# MotoLogger_Schematic.net
KiCad netlist of a schematic drawn in EasyEDA
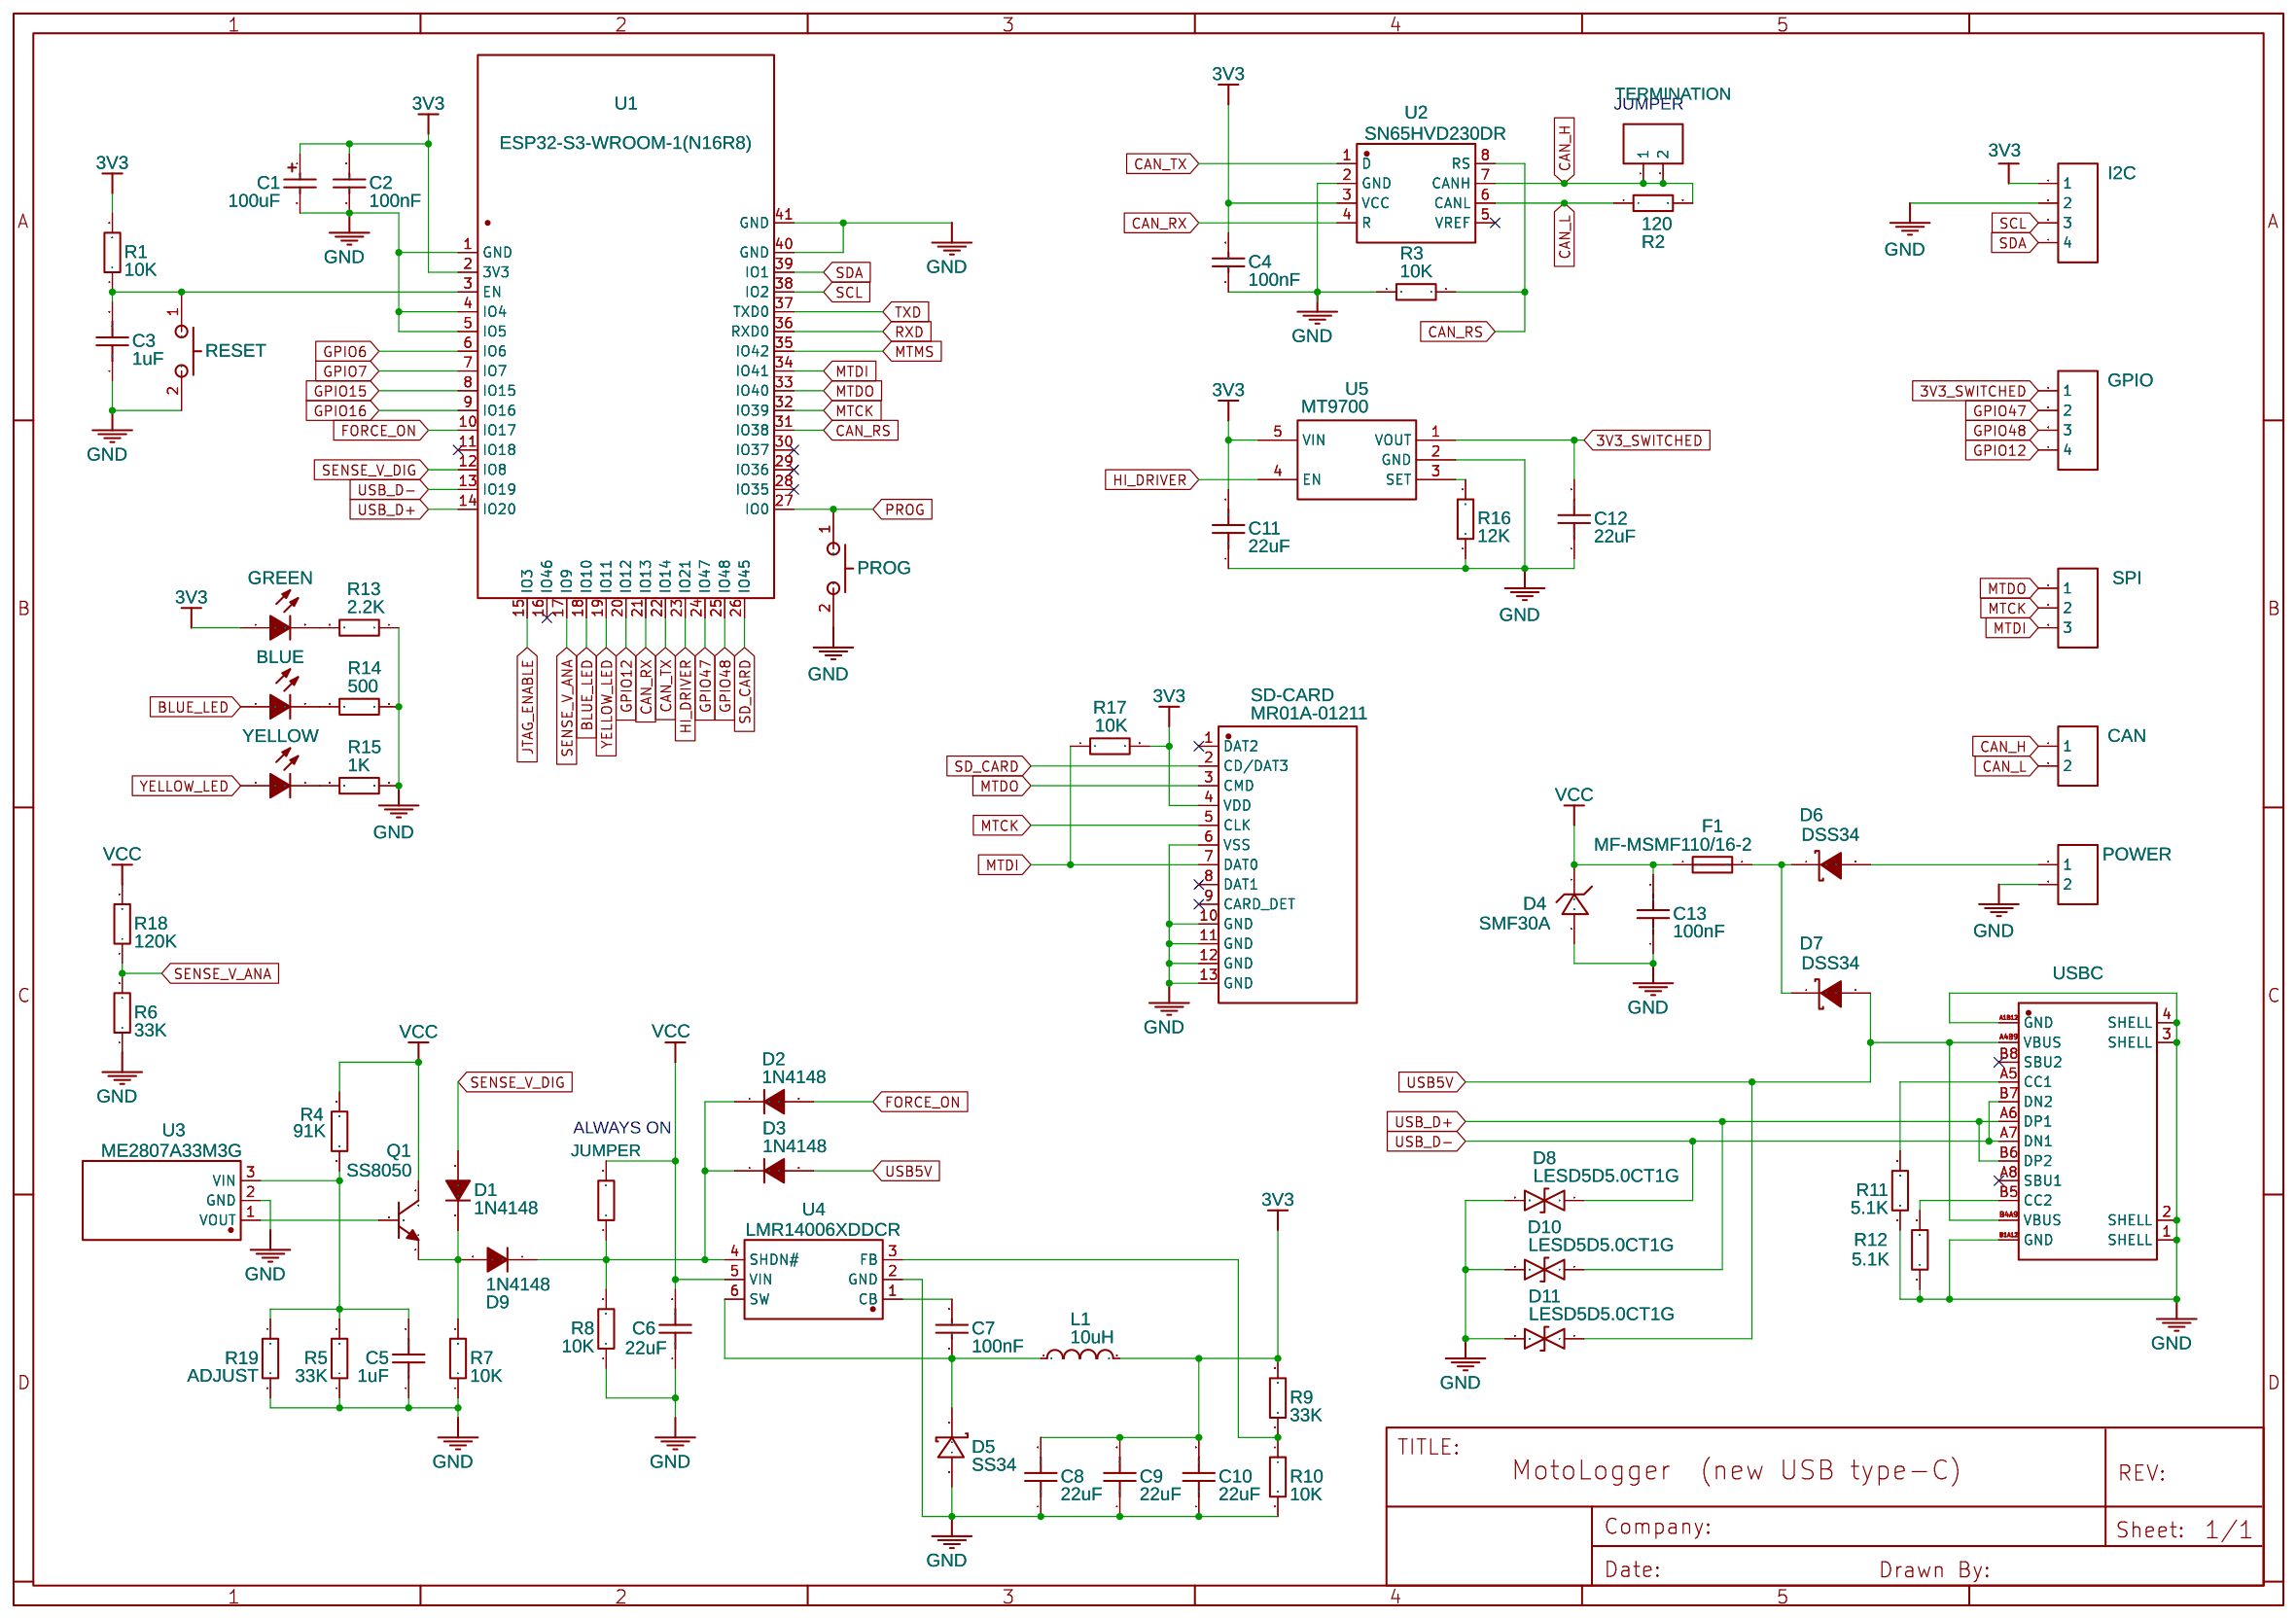
[diagram p0: schematic sheet]

(export (version "E")
  (design (tool "Eeschema 10.0.6"))
  (components
    (comp (ref "BLUE")
      (value "19-217/BHC-ZL1M2RY/3T")
      (fields (field (name "Manufacturer") "EVERLIGHT"))
      (libsource (lib "") (part "19-217/BHC-ZL1M2RY/3T"))
    )
    (comp (ref "C1")
      (value "100uF")
      (fields (field (name "Manufacturer Part") "TAJB107K006RNJ") (field (name "Manufacturer") "AVX"))
      (libsource (lib "") (part "TAJB107K006RNJ"))
    )
    (comp (ref "C2")
      (value "100nF")
      (fields (field (name "Manufacturer Part") "CL05B104KO5NNNC") (field (name "Manufacturer") "SAMSUNG"))
      (libsource (lib "") (part "CL05B104KO5NNNC"))
    )
    (comp (ref "C3")
      (value "1uF")
      (fields (field (name "Manufacturer Part") "CL05A105KA5NQNC") (field (name "Manufacturer") "SAMSUNG"))
      (libsource (lib "") (part "CL05A105KA5NQNC"))
    )
    (comp (ref "C4")
      (value "100nF")
      (fields (field (name "Manufacturer Part") "CL05B104KO5NNNC") (field (name "Manufacturer") "SAMSUNG"))
      (libsource (lib "") (part "CL05B104KO5NNNC"))
    )
    (comp (ref "C5")
      (value "1uF")
      (fields (field (name "Manufacturer Part") "CL05A105KA5NQNC") (field (name "Manufacturer") "SAMSUNG"))
      (libsource (lib "") (part "CL05A105KA5NQNC_1"))
    )
    (comp (ref "C6")
      (value "22uF")
      (fields
        (field (name "Manufacturer Part") "CL21A226MAYNNNE")
        (field (name "Manufacturer") "Samsung Electro-Mechanics")
      )
      (libsource (lib "") (part "CL21A226MAYNNNE"))
    )
    (comp (ref "C7")
      (value "100nF")
      (fields (field (name "Manufacturer Part") "CL05B104KO5NNNC") (field (name "Manufacturer") "SAMSUNG"))
      (libsource (lib "") (part "CL05B104KO5NNNC"))
    )
    (comp (ref "C8")
      (value "22uF")
      (fields (field (name "Manufacturer Part") "CL10A226MQ8NRNC") (field (name "Manufacturer") "SAMSUNG"))
      (libsource (lib "") (part "CL10A226MQ8NRNC"))
    )
    (comp (ref "C9")
      (value "22uF")
      (fields (field (name "Manufacturer Part") "CL10A226MQ8NRNC") (field (name "Manufacturer") "SAMSUNG"))
      (libsource (lib "") (part "CL10A226MQ8NRNC"))
    )
    (comp (ref "C10")
      (value "22uF")
      (fields (field (name "Manufacturer Part") "CL10A226MQ8NRNC") (field (name "Manufacturer") "SAMSUNG"))
      (libsource (lib "") (part "CL10A226MQ8NRNC"))
    )
    (comp (ref "C11")
      (value "22uF")
      (fields (field (name "Manufacturer Part") "CL10A226MQ8NRNC") (field (name "Manufacturer") "SAMSUNG"))
      (libsource (lib "") (part "CL10A226MQ8NRNC"))
    )
    (comp (ref "C12")
      (value "22uF")
      (fields (field (name "Manufacturer Part") "CL10A226MQ8NRNC") (field (name "Manufacturer") "SAMSUNG"))
      (libsource (lib "") (part "CL10A226MQ8NRNC"))
    )
    (comp (ref "C13")
      (value "100nF")
      (fields
        (field (name "Manufacturer Part") "CL05B104KB54PNC")
        (field (name "Manufacturer") "Samsung Electro-Mechanics")
      )
      (libsource (lib "") (part "CL05B104KB54PNC"))
    )
    (comp (ref "CAN") (value "HDR-M-2.54_1x2") (libsource (lib "") (part "HDR-M-2.54_1x2_1")))
    (comp (ref "D1")
      (value "1N4148")
      (fields (field (name "Manufacturer Part") "1N4148WS T4") (field (name "Manufacturer") "CJ"))
      (libsource (lib "") (part "1N4148WS T4_1"))
    )
    (comp (ref "D2")
      (value "1N4148")
      (fields (field (name "Manufacturer Part") "1N4148WS T4") (field (name "Manufacturer") "CJ"))
      (libsource (lib "") (part "1N4148WS T4"))
    )
    (comp (ref "D3")
      (value "1N4148")
      (fields (field (name "Manufacturer Part") "1N4148WS T4") (field (name "Manufacturer") "CJ"))
      (libsource (lib "") (part "1N4148WS T4"))
    )
    (comp (ref "D4")
      (value "SMF30A")
      (fields (field (name "Manufacturer") "DOWO"))
      (libsource (lib "") (part "SMF30A_C366558"))
    )
    (comp (ref "D5")
      (value "SS34")
      (fields (field (name "Manufacturer") "MDD"))
      (libsource (lib "") (part "SS34_C8678"))
    )
    (comp (ref "D6")
      (value "DSS34")
      (fields (field (name "Manufacturer") "STARSEA"))
      (libsource (lib "") (part "DSS34"))
    )
    (comp (ref "D7")
      (value "DSS34")
      (fields (field (name "Manufacturer") "STARSEA"))
      (libsource (lib "") (part "DSS34"))
    )
    (comp (ref "D8")
      (value "LESD5D5.0CT1G")
      (fields (field (name "Manufacturer") "Leshan Radio"))
      (libsource (lib "") (part "LESD5D5.0CT1G"))
    )
    (comp (ref "D9")
      (value "1N4148")
      (fields (field (name "Manufacturer Part") "1N4148WS T4") (field (name "Manufacturer") "CJ"))
      (libsource (lib "") (part "1N4148WS T4_2"))
    )
    (comp (ref "D10")
      (value "LESD5D5.0CT1G")
      (fields (field (name "Manufacturer") "Leshan Radio"))
      (libsource (lib "") (part "LESD5D5.0CT1G"))
    )
    (comp (ref "D11")
      (value "LESD5D5.0CT1G")
      (fields (field (name "Manufacturer") "Leshan Radio"))
      (libsource (lib "") (part "LESD5D5.0CT1G"))
    )
    (comp (ref "F1")
      (value "MF-MSMF110/16-2")
      (fields (field (name "Manufacturer") "BOURNS"))
      (libsource (lib "") (part "MF-MSMF110/16-2"))
    )
    (comp (ref "GPIO") (value "HDR-M-2.54_1x4") (libsource (lib "") (part "HDR-M-2.54_1x4_1")))
    (comp (ref "GREEN")
      (value "19-217/GHC-YR1S2/3T")
      (fields (field (name "Manufacturer") "EVERLIGHT"))
      (libsource (lib "") (part "19-217/GHC-YR1S2/3T"))
    )
    (comp (ref "I2C") (value "HDR-M-2.54_1x4") (libsource (lib "") (part "HDR-M-2.54_1x4")))
    (comp (ref "JUMPER") (value "-") (libsource (lib "") (part "0402WGF3092TCE")))
    (comp (ref "L1")
      (value "10uH")
      (fields
        (field (name "Manufacturer Part") "SLP6028S100MTT")
        (field (name "Manufacturer") "Sunltech Tech")
      )
      (libsource (lib "") (part "SLP6028S100MTT"))
    )
    (comp (ref "POWER") (value "HDR-M-2.54_1x2") (libsource (lib "") (part "HDR-M-2.54_1x2_2")))
    (comp (ref "PROG")
      (value "GT-TC029B-H025-L1N")
      (fields (field (name "Manufacturer") "G-Switch"))
      (libsource (lib "") (part "GT-TC029B-H025-L1N"))
    )
    (comp (ref "Q1")
      (value "SS8050")
      (fields (field (name "Manufacturer") "CJ"))
      (libsource (lib "") (part "SS8050_C2150"))
    )
    (comp (ref "R1")
      (value "10K")
      (fields (field (name "Manufacturer Part") "0402WGF1002TCE") (field (name "Manufacturer") "UniOhm"))
      (libsource (lib "") (part "0402WGF1002TCE"))
    )
    (comp (ref "R2")
      (value "120")
      (fields (field (name "Manufacturer Part") "RTT061200FTP") (field (name "Manufacturer") "RALEC"))
      (libsource (lib "") (part "RTT061200FTP"))
    )
    (comp (ref "R3")
      (value "10K")
      (fields (field (name "Manufacturer Part") "0402WGF1002TCE") (field (name "Manufacturer") "UniOhm"))
      (libsource (lib "") (part "0402WGF1002TCE_1"))
    )
    (comp (ref "R4")
      (value "91K")
      (fields (field (name "Manufacturer Part") "0402WGF9102TCE") (field (name "Manufacturer") "UniOhm"))
      (libsource (lib "") (part "0402WGF9102TCE_1"))
    )
    (comp (ref "R5")
      (value "33K")
      (fields (field (name "Manufacturer Part") "0402WGF3302TCE") (field (name "Manufacturer") "UniOhm"))
      (libsource (lib "") (part "0402WGF3302TCE"))
    )
    (comp (ref "R6")
      (value "33K")
      (fields (field (name "Manufacturer Part") "0402WGF3302TCE") (field (name "Manufacturer") "UniOhm"))
      (libsource (lib "") (part "0402WGF3302TCE"))
    )
    (comp (ref "R7")
      (value "10K")
      (fields (field (name "Manufacturer Part") "0402WGF1002TCE") (field (name "Manufacturer") "UniOhm"))
      (libsource (lib "") (part "0402WGF1002TCE"))
    )
    (comp (ref "R8")
      (value "10K")
      (fields (field (name "Manufacturer Part") "0402WGF1002TCE") (field (name "Manufacturer") "UniOhm"))
      (libsource (lib "") (part "0402WGF1002TCE"))
    )
    (comp (ref "R9")
      (value "33K")
      (fields (field (name "Manufacturer Part") "0402WGF3302TCE") (field (name "Manufacturer") "UniOhm"))
      (libsource (lib "") (part "0402WGF3302TCE"))
    )
    (comp (ref "R10")
      (value "10K")
      (fields (field (name "Manufacturer Part") "0402WGF1002TCE") (field (name "Manufacturer") "UniOhm"))
      (libsource (lib "") (part "0402WGF1002TCE_2"))
    )
    (comp (ref "R11")
      (value "5.1K")
      (fields (field (name "Manufacturer Part") "0402WGF5101TCE") (field (name "Manufacturer") "UniOhm"))
      (libsource (lib "") (part "0402WGF5101TCE"))
    )
    (comp (ref "R12")
      (value "5.1K")
      (fields (field (name "Manufacturer Part") "0402WGF5101TCE") (field (name "Manufacturer") "UniOhm"))
      (libsource (lib "") (part "0402WGF5101TCE"))
    )
    (comp (ref "R13")
      (value "2.2K")
      (fields (field (name "Manufacturer Part") "0402WGF2201TCE") (field (name "Manufacturer") "UniOhm"))
      (libsource (lib "") (part "0402WGF2201TCE"))
    )
    (comp (ref "R14")
      (value "500")
      (fields (field (name "Manufacturer Part") "0402WGF4700TCE") (field (name "Manufacturer") "UniOhm"))
      (libsource (lib "") (part "0402WGF1001TCE"))
    )
    (comp (ref "R15")
      (value "1K")
      (fields (field (name "Manufacturer Part") "0402WGF1001TCE") (field (name "Manufacturer") "UniOhm"))
      (libsource (lib "") (part "0402WGF1001TCE"))
    )
    (comp (ref "R16")
      (value "12K")
      (fields (field (name "Manufacturer Part") "0402WGF1202TCE") (field (name "Manufacturer") "UniOhm"))
      (libsource (lib "") (part "0402WGF1202TCE"))
    )
    (comp (ref "R17")
      (value "10K")
      (fields (field (name "Manufacturer Part") "0402WGF1002TCE") (field (name "Manufacturer") "UniOhm"))
      (libsource (lib "") (part "0402WGF1002TCE_1"))
    )
    (comp (ref "R18")
      (value "120K")
      (fields (field (name "Manufacturer Part") "0402WGF1203TCE") (field (name "Manufacturer") "UniOhm"))
      (libsource (lib "") (part "0402WGF1203TCE"))
    )
    (comp (ref "R19")
      (value "ADJUST")
      (fields (field (name "Manufacturer Part") "0402WGF9102TCE") (field (name "Manufacturer") "UniOhm"))
      (libsource (lib "") (part "0402WGF9102TCE"))
    )
    (comp (ref "RESET")
      (value "GT-TC029B-H025-L1N")
      (fields (field (name "Manufacturer") "G-Switch"))
      (libsource (lib "") (part "GT-TC029B-H025-L1N_1"))
    )
    (comp (ref "SD-CARD")
      (value "MR01A-01211")
      (fields (field (name "Manufacturer") "ATOM(爱特姆)"))
      (libsource (lib "") (part "MR01A-01211"))
    )
    (comp (ref "SPI") (value "HDR-M-2.54_1x3") (libsource (lib "") (part "HDR-M-2.54_1x3")))
    (comp (ref "TERMINATION") (value "HDR-M-2.54_1x2") (libsource (lib "") (part "HDR-M-2.54_1x2")))
    (comp (ref "U1")
      (value "ESP32-S3-WROOM-1(N16R8)")
      (fields (field (name "Manufacturer") "ESPRESSIF(乐鑫)"))
      (libsource (lib "") (part "ESP32-S3-WROOM-1(N16R8)"))
    )
    (comp (ref "U2")
      (value "SN65HVD230DR")
      (fields (field (name "Manufacturer") "TI"))
      (libsource (lib "") (part "SN65HVD230DR"))
    )
    (comp (ref "U3")
      (value "ME2807A33M3G")
      (fields (field (name "Manufacturer") "Nanjing Micro One Elec"))
      (libsource (lib "") (part "ME2807A33M3G"))
    )
    (comp (ref "U4")
      (value "LMR14006XDDCR")
      (fields (field (name "Manufacturer") "Texas Instruments"))
      (libsource (lib "") (part "LMR14006XDDCR"))
    )
    (comp (ref "U5")
      (value "MT9700")
      (fields (field (name "Manufacturer") "AEROSEMI"))
      (libsource (lib "") (part "MT9700"))
    )
    (comp (ref "USBC")
      (value "GT-USB-7010ASV")
      (fields (field (name "Manufacturer") "G-Switch(品赞)"))
      (libsource (lib "") (part "GT-USB-7010ASV"))
    )
    (comp (ref "YELLOW")
      (value "19-213/Y2C-CQ2R2L/3T(CY)")
      (fields (field (name "Manufacturer") "EVERLIGHT"))
      (libsource (lib "") (part "19-213/Y2C-CQ2R2L/3T(CY)"))
    )
  )
  (nets
    (net (code "1") (name "3V3") (class "Default")
      (node (ref "C1") (pin "1") (pinfunction "1_1") (pintype "input"))
      (node (ref "C10") (pin "2") (pinfunction "2_2") (pintype "unspecified"))
      (node (ref "C11") (pin "2") (pinfunction "2_2") (pintype "unspecified"))
      (node (ref "C2") (pin "2") (pinfunction "2_2") (pintype "input"))
      (node (ref "C4") (pin "2") (pinfunction "2_2") (pintype "input"))
      (node (ref "C8") (pin "2") (pinfunction "2_2") (pintype "unspecified"))
      (node (ref "C9") (pin "2") (pinfunction "2_2") (pintype "unspecified"))
      (node (ref "GREEN") (pin "1") (pinfunction "A_1") (pintype "input"))
      (node (ref "I2C") (pin "1") (pinfunction "1_1") (pintype "unspecified"))
      (node (ref "L1") (pin "2") (pinfunction "2_2") (pintype "unspecified"))
      (node (ref "R1") (pin "2") (pinfunction "2_2") (pintype "input"))
      (node (ref "R17") (pin "2") (pinfunction "2_2") (pintype "input"))
      (node (ref "R9") (pin "2") (pinfunction "2_2") (pintype "input"))
      (node (ref "SD-CARD") (pin "4") (pinfunction "VDD_4") (pintype "unspecified"))
      (node (ref "U1") (pin "2") (pinfunction "3V3_2") (pintype "unspecified"))
      (node (ref "U2") (pin "3") (pinfunction "VCC_3") (pintype "unspecified"))
      (node (ref "U5") (pin "5") (pinfunction "VIN_5") (pintype "unspecified"))
    )
    (net (code "2") (name "3V3_SWITCHED") (class "Default")
      (node (ref "C12") (pin "2") (pinfunction "2_2") (pintype "unspecified"))
      (node (ref "GPIO") (pin "1") (pinfunction "1_1") (pintype "unspecified"))
      (node (ref "U5") (pin "1") (pinfunction "VOUT_1") (pintype "unspecified"))
    )
    (net (code "3") (name "BLUE_LED") (class "Default")
      (node (ref "BLUE") (pin "1") (pinfunction "A_1") (pintype "input"))
      (node (ref "U1") (pin "18") (pinfunction "IO10_18") (pintype "unspecified"))
    )
    (net (code "4") (name "CAN_H") (class "Default")
      (node (ref "CAN") (pin "1") (pinfunction "1_1") (pintype "unspecified"))
      (node (ref "R2") (pin "2") (pinfunction "2_2") (pintype "unspecified"))
      (node (ref "TERMINATION") (pin "1") (pinfunction "1_1") (pintype "unspecified"))
      (node (ref "TERMINATION") (pin "2") (pinfunction "2_2") (pintype "unspecified"))
      (node (ref "U2") (pin "7") (pinfunction "CANH_7") (pintype "unspecified"))
    )
    (net (code "5") (name "CAN_L") (class "Default")
      (node (ref "CAN") (pin "2") (pinfunction "2_2") (pintype "unspecified"))
      (node (ref "R2") (pin "1") (pinfunction "1_1") (pintype "unspecified"))
      (node (ref "U2") (pin "6") (pinfunction "CANL_6") (pintype "unspecified"))
    )
    (net (code "6") (name "CAN_RS") (class "Default")
      (node (ref "R3") (pin "2") (pinfunction "2_2") (pintype "input"))
      (node (ref "U1") (pin "31") (pinfunction "IO38_31") (pintype "unspecified"))
      (node (ref "U2") (pin "8") (pinfunction "RS_8") (pintype "unspecified"))
    )
    (net (code "7") (name "CAN_RX") (class "Default")
      (node (ref "U1") (pin "21") (pinfunction "IO13_21") (pintype "unspecified"))
      (node (ref "U2") (pin "4") (pinfunction "R_4") (pintype "unspecified"))
    )
    (net (code "8") (name "CAN_TX") (class "Default")
      (node (ref "U1") (pin "22") (pinfunction "IO14_22") (pintype "unspecified"))
      (node (ref "U2") (pin "1") (pinfunction "D_1") (pintype "unspecified"))
    )
    (net (code "9") (name "FORCE_ON") (class "Default")
      (node (ref "D2") (pin "2") (pinfunction "A_2") (pintype "unspecified"))
      (node (ref "U1") (pin "10") (pinfunction "IO17_10") (pintype "unspecified"))
    )
    (net (code "10") (name "GND") (class "Default")
      (node (ref "C1") (pin "2") (pinfunction "2_2") (pintype "input"))
      (node (ref "C10") (pin "1") (pinfunction "1_1") (pintype "unspecified"))
      (node (ref "C11") (pin "1") (pinfunction "1_1") (pintype "unspecified"))
      (node (ref "C12") (pin "1") (pinfunction "1_1") (pintype "unspecified"))
      (node (ref "C13") (pin "1") (pinfunction "1_1") (pintype "unspecified"))
      (node (ref "C2") (pin "1") (pinfunction "1_1") (pintype "input"))
      (node (ref "C3") (pin "1") (pinfunction "1_1") (pintype "unspecified"))
      (node (ref "C4") (pin "1") (pinfunction "1_1") (pintype "input"))
      (node (ref "C5") (pin "1") (pinfunction "1_1") (pintype "unspecified"))
      (node (ref "C6") (pin "1") (pinfunction "1_1") (pintype "unspecified"))
      (node (ref "C8") (pin "1") (pinfunction "1_1") (pintype "unspecified"))
      (node (ref "C9") (pin "1") (pinfunction "1_1") (pintype "unspecified"))
      (node (ref "D10") (pin "2") (pinfunction "2_2") (pintype "unspecified"))
      (node (ref "D11") (pin "2") (pinfunction "2_2") (pintype "unspecified"))
      (node (ref "D4") (pin "2") (pinfunction "2_2") (pintype "unspecified"))
      (node (ref "D5") (pin "2") (pinfunction "A_2") (pintype "unspecified"))
      (node (ref "D8") (pin "2") (pinfunction "2_2") (pintype "unspecified"))
      (node (ref "I2C") (pin "2") (pinfunction "2_2") (pintype "unspecified"))
      (node (ref "POWER") (pin "2") (pinfunction "2_2") (pintype "unspecified"))
      (node (ref "PROG") (pin "2") (pinfunction "2_2") (pintype "unspecified"))
      (node (ref "R10") (pin "2") (pinfunction "2_2") (pintype "input"))
      (node (ref "R11") (pin "1") (pinfunction "1_1") (pintype "input"))
      (node (ref "R12") (pin "1") (pinfunction "1_1") (pintype "input"))
      (node (ref "R13") (pin "1") (pinfunction "1_1") (pintype "input"))
      (node (ref "R14") (pin "2") (pinfunction "2_2") (pintype "input"))
      (node (ref "R15") (pin "2") (pinfunction "2_2") (pintype "input"))
      (node (ref "R16") (pin "1") (pinfunction "1_1") (pintype "input"))
      (node (ref "R19") (pin "2") (pinfunction "2_2") (pintype "input"))
      (node (ref "R3") (pin "1") (pinfunction "1_1") (pintype "input"))
      (node (ref "R5") (pin "1") (pinfunction "1_1") (pintype "input"))
      (node (ref "R6") (pin "1") (pinfunction "1_1") (pintype "input"))
      (node (ref "R7") (pin "1") (pinfunction "1_1") (pintype "input"))
      (node (ref "R8") (pin "1") (pinfunction "1_1") (pintype "input"))
      (node (ref "RESET") (pin "2") (pinfunction "2_2") (pintype "unspecified"))
      (node (ref "SD-CARD") (pin "10") (pinfunction "GND_10") (pintype "unspecified"))
      (node (ref "SD-CARD") (pin "11") (pinfunction "GND_11") (pintype "unspecified"))
      (node (ref "SD-CARD") (pin "12") (pinfunction "GND_12") (pintype "unspecified"))
      (node (ref "SD-CARD") (pin "13") (pinfunction "GND_13") (pintype "unspecified"))
      (node (ref "SD-CARD") (pin "6") (pinfunction "VSS_6") (pintype "unspecified"))
      (node (ref "U1") (pin "1") (pinfunction "GND_1") (pintype "unspecified"))
      (node (ref "U1") (pin "4") (pinfunction "IO4_4") (pintype "unspecified"))
      (node (ref "U1") (pin "40") (pinfunction "GND_40") (pintype "unspecified"))
      (node (ref "U1") (pin "41") (pinfunction "GND_41") (pintype "unspecified"))
      (node (ref "U1") (pin "5") (pinfunction "IO5_5") (pintype "unspecified"))
      (node (ref "U2") (pin "2") (pinfunction "GND_2") (pintype "unspecified"))
      (node (ref "U3") (pin "2") (pinfunction "GND_2") (pintype "unspecified"))
      (node (ref "U4") (pin "2") (pinfunction "GND_2") (pintype "unspecified"))
      (node (ref "U5") (pin "2") (pinfunction "GND_2") (pintype "unspecified"))
      (node (ref "USBC") (pin "1") (pinfunction "SHELL_1") (pintype "unspecified"))
      (node (ref "USBC") (pin "2") (pinfunction "SHELL_2") (pintype "unspecified"))
      (node (ref "USBC") (pin "3") (pinfunction "SHELL_3") (pintype "unspecified"))
      (node (ref "USBC") (pin "4") (pinfunction "SHELL_4") (pintype "unspecified"))
      (node (ref "USBC") (pin "A1B12") (pinfunction "GND_A1B12") (pintype "unspecified"))
      (node (ref "USBC") (pin "B1A12") (pinfunction "GND_B1A12") (pintype "unspecified"))
    )
    (net (code "11") (name "GPIO6") (class "Default")
      (node (ref "U1") (pin "6") (pinfunction "IO6_6") (pintype "unspecified"))
    )
    (net (code "12") (name "GPIO7") (class "Default")
      (node (ref "U1") (pin "7") (pinfunction "IO7_7") (pintype "unspecified"))
    )
    (net (code "13") (name "GPIO12") (class "Default")
      (node (ref "GPIO") (pin "4") (pinfunction "4_4") (pintype "unspecified"))
      (node (ref "U1") (pin "20") (pinfunction "IO12_20") (pintype "unspecified"))
    )
    (net (code "14") (name "GPIO15") (class "Default")
      (node (ref "U1") (pin "8") (pinfunction "IO15_8") (pintype "unspecified"))
    )
    (net (code "15") (name "GPIO16") (class "Default")
      (node (ref "U1") (pin "9") (pinfunction "IO16_9") (pintype "unspecified"))
    )
    (net (code "16") (name "GPIO47") (class "Default")
      (node (ref "GPIO") (pin "2") (pinfunction "2_2") (pintype "unspecified"))
      (node (ref "U1") (pin "24") (pinfunction "IO47_24") (pintype "unspecified"))
    )
    (net (code "17") (name "GPIO48") (class "Default")
      (node (ref "GPIO") (pin "3") (pinfunction "3_3") (pintype "unspecified"))
      (node (ref "U1") (pin "25") (pinfunction "IO48_25") (pintype "unspecified"))
    )
    (net (code "18") (name "HI_DRIVER") (class "Default")
      (node (ref "U1") (pin "23") (pinfunction "IO21_23") (pintype "unspecified"))
      (node (ref "U5") (pin "4") (pinfunction "EN_4") (pintype "unspecified"))
    )
    (net (code "19") (name "JTAG_ENABLE") (class "Default")
      (node (ref "U1") (pin "15") (pinfunction "IO3_15") (pintype "unspecified"))
    )
    (net (code "20") (name "MTCK") (class "Default")
      (node (ref "SD-CARD") (pin "5") (pinfunction "CLK_5") (pintype "unspecified"))
      (node (ref "SPI") (pin "2") (pinfunction "2_2") (pintype "input"))
      (node (ref "U1") (pin "32") (pinfunction "IO39_32") (pintype "unspecified"))
    )
    (net (code "21") (name "MTDI") (class "Default")
      (node (ref "R17") (pin "1") (pinfunction "1_1") (pintype "input"))
      (node (ref "SD-CARD") (pin "7") (pinfunction "DAT0_7") (pintype "unspecified"))
      (node (ref "SPI") (pin "3") (pinfunction "3_3") (pintype "input"))
      (node (ref "U1") (pin "34") (pinfunction "IO41_34") (pintype "unspecified"))
    )
    (net (code "22") (name "MTDO") (class "Default")
      (node (ref "SD-CARD") (pin "3") (pinfunction "CMD_3") (pintype "unspecified"))
      (node (ref "SPI") (pin "1") (pinfunction "1_1") (pintype "input"))
      (node (ref "U1") (pin "33") (pinfunction "IO40_33") (pintype "unspecified"))
    )
    (net (code "23") (name "MTMS") (class "Default")
      (node (ref "U1") (pin "35") (pinfunction "IO42_35") (pintype "unspecified"))
    )
    (net (code "24") (name "Net-(BLUE-C)") (class "Default")
      (node (ref "BLUE") (pin "2") (pinfunction "C_2") (pintype "input"))
      (node (ref "R14") (pin "1") (pinfunction "1_1") (pintype "input"))
    )
    (net (code "25") (name "Net-(D1-K)") (class "Default")
      (node (ref "D1") (pin "1") (pinfunction "K_1") (pintype "unspecified"))
      (node (ref "D9") (pin "2") (pinfunction "A_2") (pintype "unspecified"))
      (node (ref "Q1") (pin "2") (pinfunction "E_2") (pintype "unspecified"))
      (node (ref "R7") (pin "2") (pinfunction "2_2") (pintype "input"))
    )
    (net (code "26") (name "Net-(D2-K)") (class "Default")
      (node (ref "D2") (pin "1") (pinfunction "K_1") (pintype "unspecified"))
      (node (ref "D3") (pin "1") (pinfunction "K_1") (pintype "unspecified"))
      (node (ref "D9") (pin "1") (pinfunction "K_1") (pintype "unspecified"))
      (node (ref "JUMPER") (pin "1") (pinfunction "1_1") (pintype "unspecified"))
      (node (ref "R8") (pin "2") (pinfunction "2_2") (pintype "input"))
      (node (ref "U4") (pin "4") (pinfunction "SHDN#_4") (pintype "unspecified"))
    )
    (net (code "27") (name "Net-(D5-K)") (class "Default")
      (node (ref "C7") (pin "1") (pinfunction "1_1") (pintype "input"))
      (node (ref "D5") (pin "1") (pinfunction "K_1") (pintype "unspecified"))
      (node (ref "L1") (pin "1") (pinfunction "1_1") (pintype "unspecified"))
      (node (ref "U4") (pin "6") (pinfunction "SW_6") (pintype "unspecified"))
    )
    (net (code "28") (name "Net-(D6-A)") (class "Default")
      (node (ref "D6") (pin "2") (pinfunction "A_2") (pintype "unspecified"))
      (node (ref "POWER") (pin "1") (pinfunction "1_1") (pintype "unspecified"))
    )
    (net (code "29") (name "Net-(D6-K)") (class "Default")
      (node (ref "D6") (pin "1") (pinfunction "K_1") (pintype "unspecified"))
      (node (ref "D7") (pin "1") (pinfunction "K_1") (pintype "unspecified"))
      (node (ref "F1") (pin "2") (pinfunction "2_2") (pintype "unspecified"))
    )
    (net (code "30") (name "Net-(GREEN-C)") (class "Default")
      (node (ref "GREEN") (pin "2") (pinfunction "C_2") (pintype "input"))
      (node (ref "R13") (pin "2") (pinfunction "2_2") (pintype "input"))
    )
    (net (code "31") (name "Net-(Q1-B)") (class "Default")
      (node (ref "Q1") (pin "1") (pinfunction "B_1") (pintype "unspecified"))
      (node (ref "U3") (pin "1") (pinfunction "VOUT_1") (pintype "unspecified"))
    )
    (net (code "32") (name "Net-(U1-EN)") (class "Default")
      (node (ref "C3") (pin "2") (pinfunction "2_2") (pintype "unspecified"))
      (node (ref "R1") (pin "1") (pinfunction "1_1") (pintype "input"))
      (node (ref "RESET") (pin "1") (pinfunction "1_1") (pintype "unspecified"))
      (node (ref "U1") (pin "3") (pinfunction "EN_3") (pintype "unspecified"))
    )
    (net (code "33") (name "Net-(U3-VIN)") (class "Default")
      (node (ref "C5") (pin "2") (pinfunction "2_2") (pintype "unspecified"))
      (node (ref "R19") (pin "1") (pinfunction "1_1") (pintype "input"))
      (node (ref "R4") (pin "1") (pinfunction "1_1") (pintype "input"))
      (node (ref "R5") (pin "2") (pinfunction "2_2") (pintype "input"))
      (node (ref "U3") (pin "3") (pinfunction "VIN_3") (pintype "unspecified"))
    )
    (net (code "34") (name "Net-(U4-CB)") (class "Default")
      (node (ref "C7") (pin "2") (pinfunction "2_2") (pintype "input"))
      (node (ref "U4") (pin "1") (pinfunction "CB_1") (pintype "unspecified"))
    )
    (net (code "35") (name "Net-(U4-FB)") (class "Default")
      (node (ref "R10") (pin "1") (pinfunction "1_1") (pintype "input"))
      (node (ref "R9") (pin "1") (pinfunction "1_1") (pintype "input"))
      (node (ref "U4") (pin "3") (pinfunction "FB_3") (pintype "unspecified"))
    )
    (net (code "36") (name "Net-(U5-SET)") (class "Default")
      (node (ref "R16") (pin "2") (pinfunction "2_2") (pintype "input"))
      (node (ref "U5") (pin "3") (pinfunction "SET_3") (pintype "unspecified"))
    )
    (net (code "37") (name "Net-(USBC-CC1)") (class "Default")
      (node (ref "R11") (pin "2") (pinfunction "2_2") (pintype "input"))
      (node (ref "USBC") (pin "A5") (pinfunction "CC1_A5") (pintype "unspecified"))
    )
    (net (code "38") (name "Net-(USBC-CC2)") (class "Default")
      (node (ref "R12") (pin "2") (pinfunction "2_2") (pintype "input"))
      (node (ref "USBC") (pin "B5") (pinfunction "CC2_B5") (pintype "unspecified"))
    )
    (net (code "39") (name "Net-(YELLOW-C)") (class "Default")
      (node (ref "R15") (pin "1") (pinfunction "1_1") (pintype "input"))
      (node (ref "YELLOW") (pin "2") (pinfunction "C_2") (pintype "input"))
    )
    (net (code "40") (name "PROG") (class "Default")
      (node (ref "PROG") (pin "1") (pinfunction "1_1") (pintype "unspecified"))
      (node (ref "U1") (pin "27") (pinfunction "IO0_27") (pintype "unspecified"))
    )
    (net (code "41") (name "RXD") (class "Default")
      (node (ref "U1") (pin "36") (pinfunction "RXD0_36") (pintype "unspecified"))
    )
    (net (code "42") (name "SCL") (class "Default")
      (node (ref "I2C") (pin "3") (pinfunction "3_3") (pintype "unspecified"))
      (node (ref "U1") (pin "38") (pinfunction "IO2_38") (pintype "unspecified"))
    )
    (net (code "43") (name "SDA") (class "Default")
      (node (ref "I2C") (pin "4") (pinfunction "4_4") (pintype "unspecified"))
      (node (ref "U1") (pin "39") (pinfunction "IO1_39") (pintype "unspecified"))
    )
    (net (code "44") (name "SD_CARD") (class "Default")
      (node (ref "SD-CARD") (pin "2") (pinfunction "CD/DAT3_2") (pintype "unspecified"))
      (node (ref "U1") (pin "26") (pinfunction "IO45_26") (pintype "unspecified"))
    )
    (net (code "45") (name "SENSE_V_ANA") (class "Default")
      (node (ref "R18") (pin "1") (pinfunction "1_1") (pintype "input"))
      (node (ref "R6") (pin "2") (pinfunction "2_2") (pintype "input"))
      (node (ref "U1") (pin "17") (pinfunction "IO9_17") (pintype "unspecified"))
    )
    (net (code "46") (name "SENSE_V_DIG") (class "Default")
      (node (ref "D1") (pin "2") (pinfunction "A_2") (pintype "unspecified"))
      (node (ref "U1") (pin "12") (pinfunction "IO8_12") (pintype "unspecified"))
    )
    (net (code "47") (name "TXD") (class "Default")
      (node (ref "U1") (pin "37") (pinfunction "TXD0_37") (pintype "unspecified"))
    )
    (net (code "48") (name "USB5V") (class "Default")
      (node (ref "D11") (pin "1") (pinfunction "1_1") (pintype "unspecified"))
      (node (ref "D3") (pin "2") (pinfunction "A_2") (pintype "unspecified"))
      (node (ref "D7") (pin "2") (pinfunction "A_2") (pintype "unspecified"))
      (node (ref "USBC") (pin "A4B9") (pinfunction "VBUS_A4B9") (pintype "unspecified"))
      (node (ref "USBC") (pin "B4A9") (pinfunction "VBUS_B4A9") (pintype "unspecified"))
    )
    (net (code "49") (name "USB_D+") (class "Default")
      (node (ref "D10") (pin "1") (pinfunction "1_1") (pintype "unspecified"))
      (node (ref "U1") (pin "14") (pinfunction "IO20_14") (pintype "unspecified"))
      (node (ref "USBC") (pin "A6") (pinfunction "DP1_A6") (pintype "unspecified"))
      (node (ref "USBC") (pin "B6") (pinfunction "DP2_B6") (pintype "unspecified"))
    )
    (net (code "50") (name "USB_D-") (class "Default")
      (node (ref "D8") (pin "1") (pinfunction "1_1") (pintype "unspecified"))
      (node (ref "U1") (pin "13") (pinfunction "IO19_13") (pintype "unspecified"))
      (node (ref "USBC") (pin "A7") (pinfunction "DN1_A7") (pintype "unspecified"))
      (node (ref "USBC") (pin "B7") (pinfunction "DN2_B7") (pintype "unspecified"))
    )
    (net (code "51") (name "VCC") (class "Default")
      (node (ref "C13") (pin "2") (pinfunction "2_2") (pintype "unspecified"))
      (node (ref "C6") (pin "2") (pinfunction "2_2") (pintype "unspecified"))
      (node (ref "D4") (pin "1") (pinfunction "1_1") (pintype "unspecified"))
      (node (ref "F1") (pin "1") (pinfunction "1_1") (pintype "unspecified"))
      (node (ref "JUMPER") (pin "2") (pinfunction "2_2") (pintype "unspecified"))
      (node (ref "Q1") (pin "3") (pinfunction "C_3") (pintype "unspecified"))
      (node (ref "R18") (pin "2") (pinfunction "2_2") (pintype "input"))
      (node (ref "R4") (pin "2") (pinfunction "2_2") (pintype "input"))
      (node (ref "U4") (pin "5") (pinfunction "VIN_5") (pintype "unspecified"))
    )
    (net (code "52") (name "YELLOW_LED") (class "Default")
      (node (ref "U1") (pin "19") (pinfunction "IO11_19") (pintype "unspecified"))
      (node (ref "YELLOW") (pin "1") (pinfunction "A_1") (pintype "input"))
    )
    (net (code "53") (name "unconnected-(SD-CARD-CARD_DET-Pad9)") (class "Default")
      (node (ref "SD-CARD") (pin "9") (pinfunction "CARD_DET_9") (pintype "unspecified+no_connect"))
    )
    (net (code "54") (name "unconnected-(SD-CARD-DAT1-Pad8)") (class "Default")
      (node (ref "SD-CARD") (pin "8") (pinfunction "DAT1_8") (pintype "unspecified+no_connect"))
    )
    (net (code "55") (name "unconnected-(SD-CARD-DAT2-Pad1)") (class "Default")
      (node (ref "SD-CARD") (pin "1") (pinfunction "DAT2_1") (pintype "unspecified+no_connect"))
    )
    (net (code "56") (name "unconnected-(U1-IO18-Pad11)") (class "Default")
      (node (ref "U1") (pin "11") (pinfunction "IO18_11") (pintype "unspecified+no_connect"))
    )
    (net (code "57") (name "unconnected-(U1-IO35-Pad28)") (class "Default")
      (node (ref "U1") (pin "28") (pinfunction "IO35_28") (pintype "unspecified+no_connect"))
    )
    (net (code "58") (name "unconnected-(U1-IO36-Pad29)") (class "Default")
      (node (ref "U1") (pin "29") (pinfunction "IO36_29") (pintype "unspecified+no_connect"))
    )
    (net (code "59") (name "unconnected-(U1-IO37-Pad30)") (class "Default")
      (node (ref "U1") (pin "30") (pinfunction "IO37_30") (pintype "unspecified+no_connect"))
    )
    (net (code "60") (name "unconnected-(U1-IO46-Pad16)") (class "Default")
      (node (ref "U1") (pin "16") (pinfunction "IO46_16") (pintype "unspecified+no_connect"))
    )
    (net (code "61") (name "unconnected-(U2-VREF-Pad5)") (class "Default")
      (node (ref "U2") (pin "5") (pinfunction "VREF_5") (pintype "unspecified+no_connect"))
    )
    (net (code "62") (name "unconnected-(USBC-SBU1-PadA8)") (class "Default")
      (node (ref "USBC") (pin "A8") (pinfunction "SBU1_A8") (pintype "unspecified+no_connect"))
    )
    (net (code "63") (name "unconnected-(USBC-SBU2-PadB8)") (class "Default")
      (node (ref "USBC") (pin "B8") (pinfunction "SBU2_B8") (pintype "unspecified+no_connect"))
    )
  )
)
